# jardim.net
KiCad netlist of a schematic drawn in EAGLE
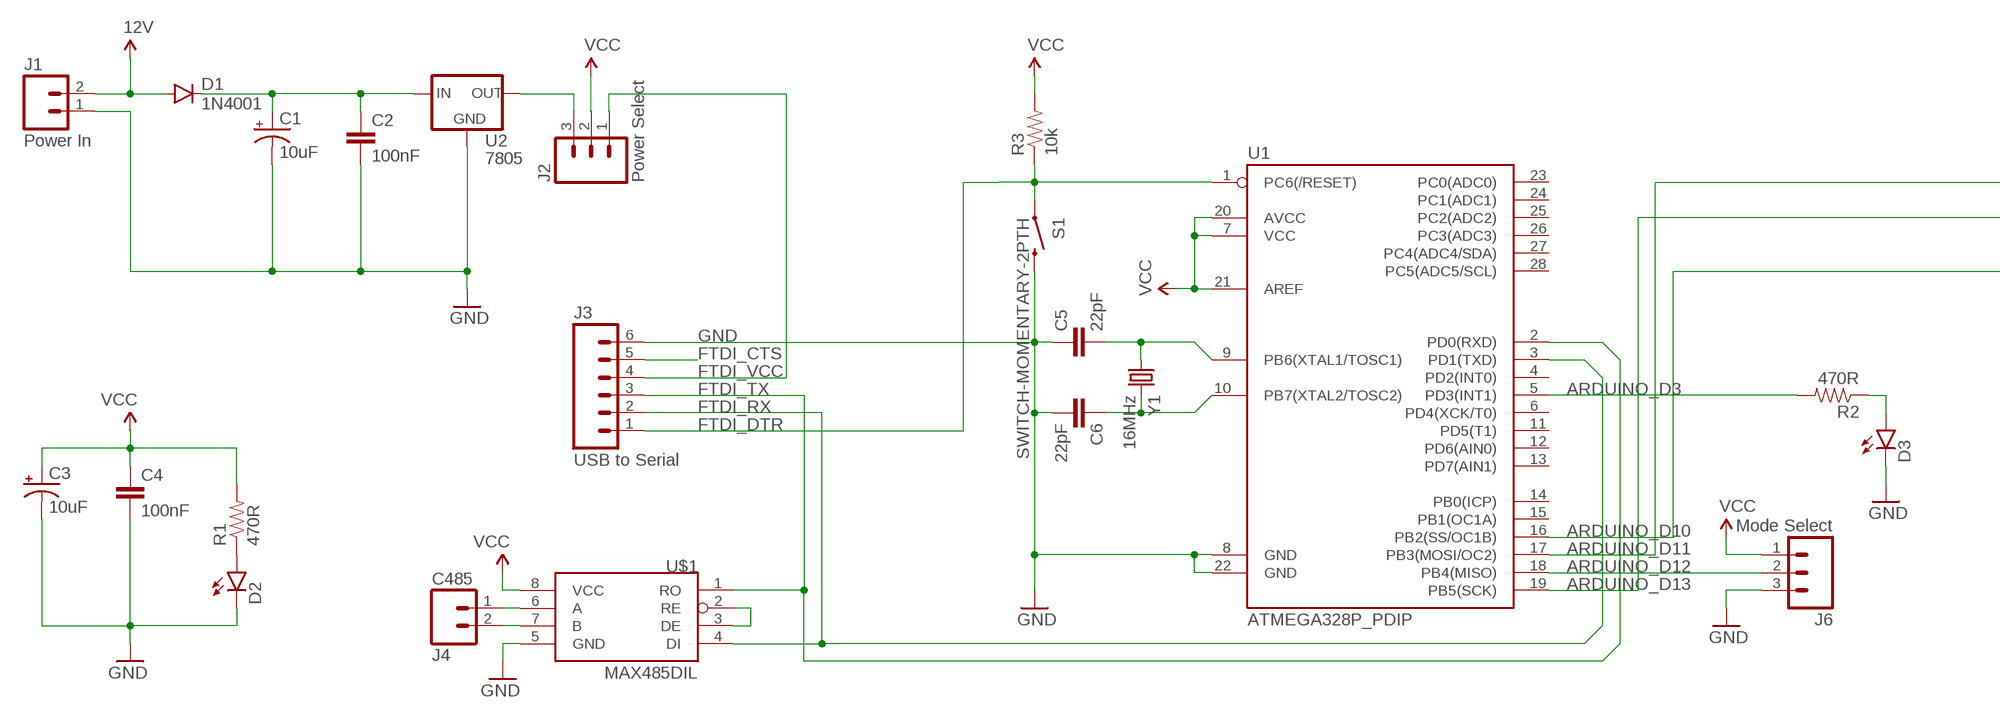
[diagram p0: schematic, sheet 1, part 1 of 2]
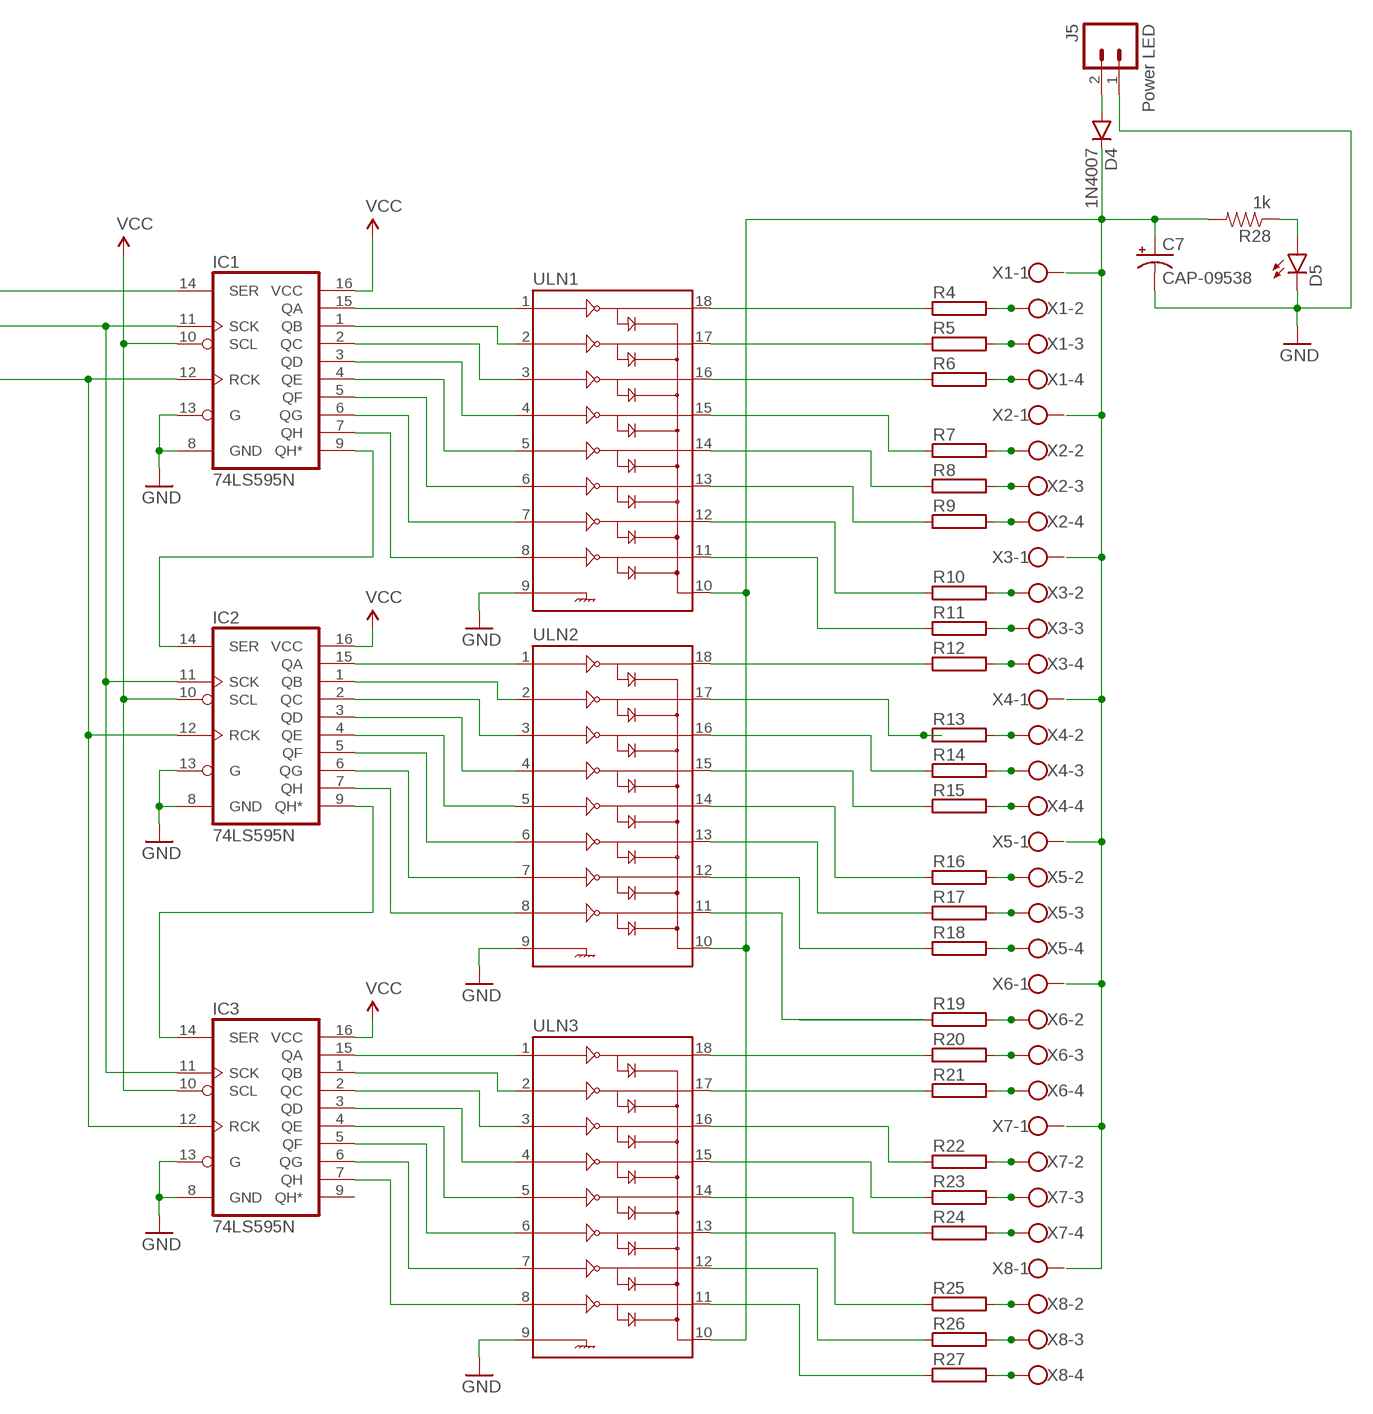
[diagram p1: schematic, sheet 1, part 2 of 2]

(export (version "E")
  (design (tool "Eeschema 10.0.6"))
  (components
    (comp (ref "C1")
      (value "10uF")
      (footprint "eagle-import:CPOL-RADIAL-10UF-25V")
      (libsource (lib "eagle-import") (part "CAP_POLPTH2"))
    )
    (comp (ref "C2")
      (value "100nF")
      (footprint "eagle-import:CAP-PTH-SMALL-KIT")
      (libsource (lib "eagle-import") (part "0.1UF-50V-20%(PTH)KIT-EZ"))
    )
    (comp (ref "C3")
      (value "10uF")
      (footprint "eagle-import:CPOL-RADIAL-10UF-25V")
      (libsource (lib "eagle-import") (part "CAP_POLPTH2"))
    )
    (comp (ref "C4")
      (value "100nF")
      (footprint "eagle-import:CAP-PTH-SMALL-KIT")
      (libsource (lib "eagle-import") (part "0.1UF-50V-20%(PTH)KIT-EZ"))
    )
    (comp (ref "C5")
      (value "22pF")
      (footprint "eagle-import:CAP-PTH-SMALL-KIT")
      (libsource (lib "eagle-import") (part "CAPKIT"))
    )
    (comp (ref "C6")
      (value "22pF")
      (footprint "eagle-import:CAP-PTH-SMALL-KIT")
      (libsource (lib "eagle-import") (part "CAPKIT"))
    )
    (comp (ref "C7")
      (value "CAP-09538")
      (footprint "eagle-import:CPOL-RADIAL-1000UF-25V")
      (libsource (lib "eagle-import") (part "1000UF-25V(PTH)"))
    )
    (comp (ref "D1")
      (value "1N4001")
      (footprint "eagle-import:DIODE-1N4001-KIT")
      (libsource (lib "eagle-import") (part "DIODEKIT2"))
    )
    (comp (ref "D2")
      (value "LED3MM")
      (footprint "eagle-import:LED3MM")
      (libsource (lib "eagle-import") (part "LED3MM"))
    )
    (comp (ref "D3")
      (value "LED3MM")
      (footprint "eagle-import:LED3MM")
      (libsource (lib "eagle-import") (part "LED3MM"))
    )
    (comp (ref "D4")
      (value "1N4007")
      (footprint "eagle-import:DIODE-1N4001")
      (libsource (lib "eagle-import") (part "DIODEPTH"))
    )
    (comp (ref "D5")
      (value "LED3MM")
      (footprint "eagle-import:LED3MM")
      (libsource (lib "eagle-import") (part "LED3MM"))
    )
    (comp (ref "IC1")
      (value "74LS595N")
      (footprint "eagle-import:DIL16")
      (libsource (lib "eagle-import") (part "74595NLS"))
    )
    (comp (ref "IC2")
      (value "74LS595N")
      (footprint "eagle-import:DIL16")
      (libsource (lib "eagle-import") (part "74595NLS"))
    )
    (comp (ref "IC3")
      (value "74LS595N")
      (footprint "eagle-import:DIL16")
      (libsource (lib "eagle-import") (part "74595NLS"))
    )
    (comp (ref "J1")
      (value "Power In")
      (footprint "eagle-import:SCREWTERMINAL-5MM-2")
      (libsource (lib "eagle-import") (part "M025MM"))
    )
    (comp (ref "J2")
      (value "Power Select")
      (footprint "eagle-import:1X03")
      (libsource (lib "eagle-import") (part "M03PTH"))
    )
    (comp (ref "J3")
      (value "USB to Serial")
      (footprint "eagle-import:1X06")
      (libsource (lib "eagle-import") (part "M06SILK_FEMALE_PTH"))
    )
    (comp (ref "J4")
      (value "C485")
      (footprint "eagle-import:SCREWTERMINAL-5MM-2")
      (libsource (lib "eagle-import") (part "M025MM"))
    )
    (comp (ref "J5")
      (value "Power LED")
      (footprint "eagle-import:SCREWTERMINAL-5MM-2")
      (libsource (lib "eagle-import") (part "M025MM"))
    )
    (comp (ref "J6")
      (value "Mode Select")
      (footprint "eagle-import:1X03")
      (libsource (lib "eagle-import") (part "M03PTH"))
    )
    (comp (ref "R1")
      (value "470R")
      (footprint "eagle-import:AXIAL-0.4")
      (libsource (lib "eagle-import") (part "RESISTORPTH-1/4W"))
    )
    (comp (ref "R2")
      (value "470R")
      (footprint "eagle-import:AXIAL-0.4")
      (libsource (lib "eagle-import") (part "RESISTORPTH-1/4W"))
    )
    (comp (ref "R3")
      (value "10k")
      (footprint "eagle-import:AXIAL-0.4")
      (libsource (lib "eagle-import") (part "RESISTORPTH-1/4W"))
    )
    (comp (ref "R4")
      (value "RCA4080")
      (footprint "eagle-import:CA4080")
      (libsource (lib "eagle-import") (part "RCA4080"))
    )
    (comp (ref "R5")
      (value "RCA4080")
      (footprint "eagle-import:CA4080")
      (libsource (lib "eagle-import") (part "RCA4080"))
    )
    (comp (ref "R6")
      (value "RCA4080")
      (footprint "eagle-import:CA4080")
      (libsource (lib "eagle-import") (part "RCA4080"))
    )
    (comp (ref "R7")
      (value "RCA4080")
      (footprint "eagle-import:CA4080")
      (libsource (lib "eagle-import") (part "RCA4080"))
    )
    (comp (ref "R8")
      (value "RCA4080")
      (footprint "eagle-import:CA4080")
      (libsource (lib "eagle-import") (part "RCA4080"))
    )
    (comp (ref "R9")
      (value "RCA4080")
      (footprint "eagle-import:CA4080")
      (libsource (lib "eagle-import") (part "RCA4080"))
    )
    (comp (ref "R10")
      (value "RCA4080")
      (footprint "eagle-import:CA4080")
      (libsource (lib "eagle-import") (part "RCA4080"))
    )
    (comp (ref "R11")
      (value "RCA4080")
      (footprint "eagle-import:CA4080")
      (libsource (lib "eagle-import") (part "RCA4080"))
    )
    (comp (ref "R12")
      (value "RCA4080")
      (footprint "eagle-import:CA4080")
      (libsource (lib "eagle-import") (part "RCA4080"))
    )
    (comp (ref "R13")
      (value "RCA4080")
      (footprint "eagle-import:CA4080")
      (libsource (lib "eagle-import") (part "RCA4080"))
    )
    (comp (ref "R14")
      (value "RCA4080")
      (footprint "eagle-import:CA4080")
      (libsource (lib "eagle-import") (part "RCA4080"))
    )
    (comp (ref "R15")
      (value "RCA4080")
      (footprint "eagle-import:CA4080")
      (libsource (lib "eagle-import") (part "RCA4080"))
    )
    (comp (ref "R16")
      (value "RCA4080")
      (footprint "eagle-import:CA4080")
      (libsource (lib "eagle-import") (part "RCA4080"))
    )
    (comp (ref "R17")
      (value "RCA4080")
      (footprint "eagle-import:CA4080")
      (libsource (lib "eagle-import") (part "RCA4080"))
    )
    (comp (ref "R18")
      (value "RCA4080")
      (footprint "eagle-import:CA4080")
      (libsource (lib "eagle-import") (part "RCA4080"))
    )
    (comp (ref "R19")
      (value "RCA4080")
      (footprint "eagle-import:CA4080")
      (libsource (lib "eagle-import") (part "RCA4080"))
    )
    (comp (ref "R20")
      (value "RCA4080")
      (footprint "eagle-import:CA4080")
      (libsource (lib "eagle-import") (part "RCA4080"))
    )
    (comp (ref "R21")
      (value "RCA4080")
      (footprint "eagle-import:CA4080")
      (libsource (lib "eagle-import") (part "RCA4080"))
    )
    (comp (ref "R22")
      (value "RCA4080")
      (footprint "eagle-import:CA4080")
      (libsource (lib "eagle-import") (part "RCA4080"))
    )
    (comp (ref "R23")
      (value "RCA4080")
      (footprint "eagle-import:CA4080")
      (libsource (lib "eagle-import") (part "RCA4080"))
    )
    (comp (ref "R24")
      (value "RCA4080")
      (footprint "eagle-import:CA4080")
      (libsource (lib "eagle-import") (part "RCA4080"))
    )
    (comp (ref "R25")
      (value "RCA4080")
      (footprint "eagle-import:CA4080")
      (libsource (lib "eagle-import") (part "RCA4080"))
    )
    (comp (ref "R26")
      (value "RCA4080")
      (footprint "eagle-import:CA4080")
      (libsource (lib "eagle-import") (part "RCA4080"))
    )
    (comp (ref "R27")
      (value "RCA4080")
      (footprint "eagle-import:CA4080")
      (libsource (lib "eagle-import") (part "RCA4080"))
    )
    (comp (ref "R28")
      (value "1k")
      (footprint "eagle-import:AXIAL-0.4")
      (libsource (lib "eagle-import") (part "RESISTORPTH-1/4W"))
    )
    (comp (ref "S1")
      (value "SWITCH-MOMENTARY-2PTH")
      (footprint "eagle-import:TACTILE-PTH")
      (libsource (lib "eagle-import") (part "SWITCH-MOMENTARY-2PTH"))
    )
    (comp (ref "U$1")
      (value "MAX485DIL")
      (footprint "eagle-import:DIL08")
      (libsource (lib "eagle-import") (part "MAX485DIL"))
    )
    (comp (ref "U1")
      (value "ATMEGA328P_PDIP")
      (footprint "eagle-import:DIL28-3")
      (libsource (lib "eagle-import") (part "ATMEGA328P_PDIP"))
    )
    (comp (ref "U2")
      (value "7805")
      (footprint "eagle-import:TO-220-ALT")
      (libsource (lib "eagle-import") (part "V_REG_78XX-TO-220"))
    )
    (comp (ref "ULN1")
      (value "ULN2803DIP")
      (footprint "eagle-import:DIL18")
      (libsource (lib "eagle-import") (part "ULN2803DIP"))
    )
    (comp (ref "ULN2")
      (value "ULN2803DIP")
      (footprint "eagle-import:DIL18")
      (libsource (lib "eagle-import") (part "ULN2803DIP"))
    )
    (comp (ref "ULN3")
      (value "ULN2803DIP")
      (footprint "eagle-import:DIL18")
      (libsource (lib "eagle-import") (part "ULN2803DIP"))
    )
    (comp (ref "X1")
      (value "W237-4")
      (footprint "eagle-import:W237-4")
      (libsource (lib "eagle-import") (part "W237-4"))
    )
    (comp (ref "X2")
      (value "W237-4")
      (footprint "eagle-import:W237-4")
      (libsource (lib "eagle-import") (part "W237-4"))
    )
    (comp (ref "X3")
      (value "W237-4")
      (footprint "eagle-import:W237-4")
      (libsource (lib "eagle-import") (part "W237-4"))
    )
    (comp (ref "X4")
      (value "W237-4")
      (footprint "eagle-import:W237-4")
      (libsource (lib "eagle-import") (part "W237-4"))
    )
    (comp (ref "X5")
      (value "W237-4")
      (footprint "eagle-import:W237-4")
      (libsource (lib "eagle-import") (part "W237-4"))
    )
    (comp (ref "X6")
      (value "W237-4")
      (footprint "eagle-import:W237-4")
      (libsource (lib "eagle-import") (part "W237-4"))
    )
    (comp (ref "X7")
      (value "W237-4")
      (footprint "eagle-import:W237-4")
      (libsource (lib "eagle-import") (part "W237-4"))
    )
    (comp (ref "X8")
      (value "W237-4")
      (footprint "eagle-import:W237-4")
      (libsource (lib "eagle-import") (part "W237-4"))
    )
    (comp (ref "Y1")
      (value "16MHz")
      (footprint "eagle-import:HC49US")
      (libsource (lib "eagle-import") (part "CRYSTALHC49US"))
    )
  )
  (nets
    (net (code "1") (name "/ARDUINO_D3") (class "Default")
      (node (ref "R2") (pin "P$2") (pinfunction "2_P$2") (pintype "passive"))
      (node (ref "U1") (pin "5") (pinfunction "PD3(INT1)_5") (pintype "bidirectional"))
    )
    (net (code "2") (name "/ARDUINO_D10") (class "Default")
      (node (ref "IC1") (pin "12") (pinfunction "RCK_12") (pintype "input"))
      (node (ref "IC2") (pin "12") (pinfunction "RCK_12") (pintype "input"))
      (node (ref "IC3") (pin "12") (pinfunction "RCK_12") (pintype "input"))
      (node (ref "U1") (pin "16") (pinfunction "PB2(SS/OC1B)_16") (pintype "bidirectional"))
    )
    (net (code "3") (name "/ARDUINO_D11") (class "Default")
      (node (ref "IC1") (pin "14") (pinfunction "SER_14") (pintype "input"))
      (node (ref "U1") (pin "17") (pinfunction "PB3(MOSI/OC2)_17") (pintype "bidirectional"))
    )
    (net (code "4") (name "/ARDUINO_D12") (class "Default")
      (node (ref "J6") (pin "2") (pinfunction "2_2") (pintype "passive"))
      (node (ref "U1") (pin "18") (pinfunction "PB4(MISO)_18") (pintype "bidirectional"))
    )
    (net (code "5") (name "/ARDUINO_D13") (class "Default")
      (node (ref "IC1") (pin "11") (pinfunction "SCK_11") (pintype "input"))
      (node (ref "IC2") (pin "11") (pinfunction "SCK_11") (pintype "input"))
      (node (ref "IC3") (pin "11") (pinfunction "SCK_11") (pintype "input"))
      (node (ref "U1") (pin "19") (pinfunction "PB5(SCK)_19") (pintype "bidirectional"))
    )
    (net (code "6") (name "/FTDI_CTS") (class "Default")
      (node (ref "J3") (pin "5") (pinfunction "5_5") (pintype "passive"))
    )
    (net (code "7") (name "/FTDI_DTR") (class "Default")
      (node (ref "J3") (pin "1") (pinfunction "1_1") (pintype "passive"))
      (node (ref "R3") (pin "P$1") (pinfunction "1_P$1") (pintype "passive"))
      (node (ref "S1") (pin "1") (pinfunction "1_1") (pintype "passive"))
      (node (ref "U1") (pin "1") (pinfunction "PC6(/RESET)_1") (pintype "bidirectional"))
    )
    (net (code "8") (name "/FTDI_RX") (class "Default")
      (node (ref "J3") (pin "2") (pinfunction "2_2") (pintype "passive"))
      (node (ref "U$1") (pin "4") (pinfunction "DI_4") (pintype "bidirectional"))
      (node (ref "U1") (pin "3") (pinfunction "PD1(TXD)_3") (pintype "bidirectional"))
    )
    (net (code "9") (name "/FTDI_TX") (class "Default")
      (node (ref "J3") (pin "3") (pinfunction "3_3") (pintype "passive"))
      (node (ref "U$1") (pin "1") (pinfunction "RO_1") (pintype "bidirectional"))
      (node (ref "U1") (pin "2") (pinfunction "PD0(RXD)_2") (pintype "bidirectional"))
    )
    (net (code "10") (name "/FTDI_VCC") (class "Default")
      (node (ref "J2") (pin "1") (pinfunction "1_1") (pintype "passive"))
      (node (ref "J3") (pin "4") (pinfunction "4_4") (pintype "passive"))
    )
    (net (code "11") (name "12V") (class "Default")
      (node (ref "D1") (pin "A") (pinfunction "A_A") (pintype "passive"))
      (node (ref "J1") (pin "2") (pinfunction "2_2") (pintype "passive"))
    )
    (net (code "12") (name "GND") (class "Default")
      (node (ref "C1") (pin "2") (pinfunction "-_2") (pintype "passive"))
      (node (ref "C2") (pin "2") (pinfunction "2_2") (pintype "passive"))
      (node (ref "C3") (pin "2") (pinfunction "-_2") (pintype "passive"))
      (node (ref "C4") (pin "2") (pinfunction "2_2") (pintype "passive"))
      (node (ref "C5") (pin "1") (pinfunction "1_1") (pintype "passive"))
      (node (ref "C6") (pin "2") (pinfunction "2_2") (pintype "passive"))
      (node (ref "C7") (pin "-") (pinfunction "-_-") (pintype "passive"))
      (node (ref "D2") (pin "K") (pinfunction "C_K") (pintype "passive"))
      (node (ref "D3") (pin "K") (pinfunction "C_K") (pintype "passive"))
      (node (ref "D5") (pin "K") (pinfunction "C_K") (pintype "passive"))
      (node (ref "IC1") (pin "13") (pinfunction "G_13") (pintype "input"))
      (node (ref "IC1") (pin "8") (pinfunction "GND_8") (pintype "power_in"))
      (node (ref "IC2") (pin "13") (pinfunction "G_13") (pintype "input"))
      (node (ref "IC2") (pin "8") (pinfunction "GND_8") (pintype "power_in"))
      (node (ref "IC3") (pin "13") (pinfunction "G_13") (pintype "input"))
      (node (ref "IC3") (pin "8") (pinfunction "GND_8") (pintype "power_in"))
      (node (ref "J1") (pin "1") (pinfunction "1_1") (pintype "passive"))
      (node (ref "J3") (pin "6") (pinfunction "6_6") (pintype "passive"))
      (node (ref "J5") (pin "1") (pinfunction "1_1") (pintype "passive"))
      (node (ref "J6") (pin "3") (pinfunction "3_3") (pintype "passive"))
      (node (ref "S1") (pin "3") (pinfunction "2_3") (pintype "passive"))
      (node (ref "U$1") (pin "5") (pinfunction "GND_5") (pintype "bidirectional"))
      (node (ref "U1") (pin "22") (pinfunction "GND_22") (pintype "bidirectional"))
      (node (ref "U1") (pin "8") (pinfunction "GND_8") (pintype "bidirectional"))
      (node (ref "U2") (pin "GND") (pinfunction "GND_GND") (pintype "input"))
      (node (ref "ULN1") (pin "9") (pinfunction "9_9") (pintype "bidirectional"))
      (node (ref "ULN2") (pin "9") (pinfunction "9_9") (pintype "bidirectional"))
      (node (ref "ULN3") (pin "9") (pinfunction "9_9") (pintype "bidirectional"))
    )
    (net (code "13") (name "Net-(C1-+)") (class "Default")
      (node (ref "C1") (pin "1") (pinfunction "+_1") (pintype "passive"))
      (node (ref "C2") (pin "1") (pinfunction "1_1") (pintype "passive"))
      (node (ref "D1") (pin "C") (pinfunction "C_C") (pintype "passive"))
      (node (ref "U2") (pin "IN") (pinfunction "IN_IN") (pintype "input"))
    )
    (net (code "14") (name "Net-(D4-PadA)") (class "Default")
      (node (ref "D4") (pin "A") (pinfunction "A_A") (pintype "passive"))
      (node (ref "J5") (pin "2") (pinfunction "2_2") (pintype "passive"))
    )
    (net (code "15") (name "Net-(IC1-QA)") (class "Default")
      (node (ref "IC1") (pin "15") (pinfunction "QA_15") (pintype "tri_state"))
      (node (ref "ULN1") (pin "1") (pinfunction "1_1") (pintype "bidirectional"))
    )
    (net (code "16") (name "Net-(IC1-QB)") (class "Default")
      (node (ref "IC1") (pin "1") (pinfunction "QB_1") (pintype "tri_state"))
      (node (ref "ULN1") (pin "2") (pinfunction "2_2") (pintype "bidirectional"))
    )
    (net (code "17") (name "Net-(IC1-QC)") (class "Default")
      (node (ref "IC1") (pin "2") (pinfunction "QC_2") (pintype "tri_state"))
      (node (ref "ULN1") (pin "3") (pinfunction "3_3") (pintype "bidirectional"))
    )
    (net (code "18") (name "Net-(IC1-QD)") (class "Default")
      (node (ref "IC1") (pin "3") (pinfunction "QD_3") (pintype "tri_state"))
      (node (ref "ULN1") (pin "4") (pinfunction "4_4") (pintype "bidirectional"))
    )
    (net (code "19") (name "Net-(IC1-QE)") (class "Default")
      (node (ref "IC1") (pin "4") (pinfunction "QE_4") (pintype "tri_state"))
      (node (ref "ULN1") (pin "5") (pinfunction "5_5") (pintype "bidirectional"))
    )
    (net (code "20") (name "Net-(IC1-QF)") (class "Default")
      (node (ref "IC1") (pin "5") (pinfunction "QF_5") (pintype "tri_state"))
      (node (ref "ULN1") (pin "6") (pinfunction "6_6") (pintype "bidirectional"))
    )
    (net (code "21") (name "Net-(IC1-QG)") (class "Default")
      (node (ref "IC1") (pin "6") (pinfunction "QG_6") (pintype "tri_state"))
      (node (ref "ULN1") (pin "7") (pinfunction "7_7") (pintype "bidirectional"))
    )
    (net (code "22") (name "Net-(IC1-QH)") (class "Default")
      (node (ref "IC1") (pin "7") (pinfunction "QH_7") (pintype "tri_state"))
      (node (ref "ULN1") (pin "8") (pinfunction "8_8") (pintype "bidirectional"))
    )
    (net (code "23") (name "Net-(IC1-QH*)") (class "Default")
      (node (ref "IC1") (pin "9") (pinfunction "QH*_9") (pintype "tri_state"))
      (node (ref "IC2") (pin "14") (pinfunction "SER_14") (pintype "input"))
    )
    (net (code "24") (name "Net-(IC2-QA)") (class "Default")
      (node (ref "IC2") (pin "15") (pinfunction "QA_15") (pintype "tri_state"))
      (node (ref "ULN2") (pin "1") (pinfunction "1_1") (pintype "bidirectional"))
    )
    (net (code "25") (name "Net-(IC2-QB)") (class "Default")
      (node (ref "IC2") (pin "1") (pinfunction "QB_1") (pintype "tri_state"))
      (node (ref "ULN2") (pin "2") (pinfunction "2_2") (pintype "bidirectional"))
    )
    (net (code "26") (name "Net-(IC2-QC)") (class "Default")
      (node (ref "IC2") (pin "2") (pinfunction "QC_2") (pintype "tri_state"))
      (node (ref "ULN2") (pin "3") (pinfunction "3_3") (pintype "bidirectional"))
    )
    (net (code "27") (name "Net-(IC2-QD)") (class "Default")
      (node (ref "IC2") (pin "3") (pinfunction "QD_3") (pintype "tri_state"))
      (node (ref "ULN2") (pin "4") (pinfunction "4_4") (pintype "bidirectional"))
    )
    (net (code "28") (name "Net-(IC2-QE)") (class "Default")
      (node (ref "IC2") (pin "4") (pinfunction "QE_4") (pintype "tri_state"))
      (node (ref "ULN2") (pin "5") (pinfunction "5_5") (pintype "bidirectional"))
    )
    (net (code "29") (name "Net-(IC2-QF)") (class "Default")
      (node (ref "IC2") (pin "5") (pinfunction "QF_5") (pintype "tri_state"))
      (node (ref "ULN2") (pin "6") (pinfunction "6_6") (pintype "bidirectional"))
    )
    (net (code "30") (name "Net-(IC2-QG)") (class "Default")
      (node (ref "IC2") (pin "6") (pinfunction "QG_6") (pintype "tri_state"))
      (node (ref "ULN2") (pin "7") (pinfunction "7_7") (pintype "bidirectional"))
    )
    (net (code "31") (name "Net-(IC2-QH)") (class "Default")
      (node (ref "IC2") (pin "7") (pinfunction "QH_7") (pintype "tri_state"))
      (node (ref "ULN2") (pin "8") (pinfunction "8_8") (pintype "bidirectional"))
    )
    (net (code "32") (name "Net-(IC2-QH*)") (class "Default")
      (node (ref "IC2") (pin "9") (pinfunction "QH*_9") (pintype "tri_state"))
      (node (ref "IC3") (pin "14") (pinfunction "SER_14") (pintype "input"))
    )
    (net (code "33") (name "Net-(IC3-QA)") (class "Default")
      (node (ref "IC3") (pin "15") (pinfunction "QA_15") (pintype "tri_state"))
      (node (ref "ULN3") (pin "1") (pinfunction "1_1") (pintype "bidirectional"))
    )
    (net (code "34") (name "Net-(IC3-QB)") (class "Default")
      (node (ref "IC3") (pin "1") (pinfunction "QB_1") (pintype "tri_state"))
      (node (ref "ULN3") (pin "2") (pinfunction "2_2") (pintype "bidirectional"))
    )
    (net (code "35") (name "Net-(IC3-QC)") (class "Default")
      (node (ref "IC3") (pin "2") (pinfunction "QC_2") (pintype "tri_state"))
      (node (ref "ULN3") (pin "3") (pinfunction "3_3") (pintype "bidirectional"))
    )
    (net (code "36") (name "Net-(IC3-QD)") (class "Default")
      (node (ref "IC3") (pin "3") (pinfunction "QD_3") (pintype "tri_state"))
      (node (ref "ULN3") (pin "4") (pinfunction "4_4") (pintype "bidirectional"))
    )
    (net (code "37") (name "Net-(IC3-QE)") (class "Default")
      (node (ref "IC3") (pin "4") (pinfunction "QE_4") (pintype "tri_state"))
      (node (ref "ULN3") (pin "5") (pinfunction "5_5") (pintype "bidirectional"))
    )
    (net (code "38") (name "Net-(IC3-QF)") (class "Default")
      (node (ref "IC3") (pin "5") (pinfunction "QF_5") (pintype "tri_state"))
      (node (ref "ULN3") (pin "6") (pinfunction "6_6") (pintype "bidirectional"))
    )
    (net (code "39") (name "Net-(IC3-QG)") (class "Default")
      (node (ref "IC3") (pin "6") (pinfunction "QG_6") (pintype "tri_state"))
      (node (ref "ULN3") (pin "7") (pinfunction "7_7") (pintype "bidirectional"))
    )
    (net (code "40") (name "Net-(IC3-QH)") (class "Default")
      (node (ref "IC3") (pin "7") (pinfunction "QH_7") (pintype "tri_state"))
      (node (ref "ULN3") (pin "8") (pinfunction "8_8") (pintype "bidirectional"))
    )
    (net (code "41") (name "Net-(J2-Pad3)") (class "Default")
      (node (ref "J2") (pin "3") (pinfunction "3_3") (pintype "passive"))
      (node (ref "U2") (pin "OUT") (pinfunction "OUT_OUT") (pintype "passive"))
    )
    (net (code "42") (name "Net-(R1-1)") (class "Default")
      (node (ref "D2") (pin "A") (pinfunction "A_A") (pintype "passive"))
      (node (ref "R1") (pin "P$1") (pinfunction "1_P$1") (pintype "passive"))
    )
    (net (code "43") (name "Net-(R2-1)") (class "Default")
      (node (ref "D3") (pin "A") (pinfunction "A_A") (pintype "passive"))
      (node (ref "R2") (pin "P$1") (pinfunction "1_P$1") (pintype "passive"))
    )
    (net (code "44") (name "Net-(R4-Pad1)") (class "Default")
      (node (ref "R4") (pin "1") (pinfunction "1_1") (pintype "passive"))
      (node (ref "ULN1") (pin "18") (pinfunction "18_18") (pintype "bidirectional"))
    )
    (net (code "45") (name "Net-(R5-Pad1)") (class "Default")
      (node (ref "R5") (pin "1") (pinfunction "1_1") (pintype "passive"))
      (node (ref "ULN1") (pin "17") (pinfunction "17_17") (pintype "bidirectional"))
    )
    (net (code "46") (name "Net-(R6-Pad1)") (class "Default")
      (node (ref "R6") (pin "1") (pinfunction "1_1") (pintype "passive"))
      (node (ref "ULN1") (pin "16") (pinfunction "16_16") (pintype "bidirectional"))
    )
    (net (code "47") (name "Net-(R7-Pad1)") (class "Default")
      (node (ref "R7") (pin "1") (pinfunction "1_1") (pintype "passive"))
      (node (ref "ULN1") (pin "15") (pinfunction "15_15") (pintype "bidirectional"))
    )
    (net (code "48") (name "Net-(R8-Pad1)") (class "Default")
      (node (ref "R8") (pin "1") (pinfunction "1_1") (pintype "passive"))
      (node (ref "ULN1") (pin "14") (pinfunction "14_14") (pintype "bidirectional"))
    )
    (net (code "49") (name "Net-(R9-Pad1)") (class "Default")
      (node (ref "R9") (pin "1") (pinfunction "1_1") (pintype "passive"))
      (node (ref "ULN1") (pin "13") (pinfunction "13_13") (pintype "bidirectional"))
    )
    (net (code "50") (name "Net-(R10-Pad1)") (class "Default")
      (node (ref "R10") (pin "1") (pinfunction "1_1") (pintype "passive"))
      (node (ref "ULN1") (pin "12") (pinfunction "12_12") (pintype "bidirectional"))
    )
    (net (code "51") (name "Net-(R11-Pad1)") (class "Default")
      (node (ref "R11") (pin "1") (pinfunction "1_1") (pintype "passive"))
      (node (ref "ULN1") (pin "11") (pinfunction "11_11") (pintype "bidirectional"))
    )
    (net (code "52") (name "Net-(R12-Pad1)") (class "Default")
      (node (ref "R12") (pin "1") (pinfunction "1_1") (pintype "passive"))
      (node (ref "ULN2") (pin "18") (pinfunction "18_18") (pintype "bidirectional"))
    )
    (net (code "53") (name "Net-(R13-Pad1)") (class "Default")
      (node (ref "R13") (pin "1") (pinfunction "1_1") (pintype "passive"))
      (node (ref "ULN2") (pin "17") (pinfunction "17_17") (pintype "bidirectional"))
    )
    (net (code "54") (name "Net-(R14-Pad1)") (class "Default")
      (node (ref "R14") (pin "1") (pinfunction "1_1") (pintype "passive"))
      (node (ref "ULN2") (pin "16") (pinfunction "16_16") (pintype "bidirectional"))
    )
    (net (code "55") (name "Net-(R15-Pad1)") (class "Default")
      (node (ref "R15") (pin "1") (pinfunction "1_1") (pintype "passive"))
      (node (ref "ULN2") (pin "15") (pinfunction "15_15") (pintype "bidirectional"))
    )
    (net (code "56") (name "Net-(R16-Pad1)") (class "Default")
      (node (ref "R16") (pin "1") (pinfunction "1_1") (pintype "passive"))
      (node (ref "ULN2") (pin "14") (pinfunction "14_14") (pintype "bidirectional"))
    )
    (net (code "57") (name "Net-(R17-Pad1)") (class "Default")
      (node (ref "R17") (pin "1") (pinfunction "1_1") (pintype "passive"))
      (node (ref "ULN2") (pin "13") (pinfunction "13_13") (pintype "bidirectional"))
    )
    (net (code "58") (name "Net-(R18-Pad1)") (class "Default")
      (node (ref "R18") (pin "1") (pinfunction "1_1") (pintype "passive"))
      (node (ref "ULN2") (pin "12") (pinfunction "12_12") (pintype "bidirectional"))
    )
    (net (code "59") (name "Net-(R19-Pad1)") (class "Default")
      (node (ref "R19") (pin "1") (pinfunction "1_1") (pintype "passive"))
      (node (ref "ULN2") (pin "11") (pinfunction "11_11") (pintype "bidirectional"))
    )
    (net (code "60") (name "Net-(R20-Pad1)") (class "Default")
      (node (ref "R20") (pin "1") (pinfunction "1_1") (pintype "passive"))
      (node (ref "ULN3") (pin "18") (pinfunction "18_18") (pintype "bidirectional"))
    )
    (net (code "61") (name "Net-(R21-Pad1)") (class "Default")
      (node (ref "R21") (pin "1") (pinfunction "1_1") (pintype "passive"))
      (node (ref "ULN3") (pin "17") (pinfunction "17_17") (pintype "bidirectional"))
    )
    (net (code "62") (name "Net-(R22-Pad1)") (class "Default")
      (node (ref "R22") (pin "1") (pinfunction "1_1") (pintype "passive"))
      (node (ref "ULN3") (pin "16") (pinfunction "16_16") (pintype "bidirectional"))
    )
    (net (code "63") (name "Net-(R23-Pad1)") (class "Default")
      (node (ref "R23") (pin "1") (pinfunction "1_1") (pintype "passive"))
      (node (ref "ULN3") (pin "15") (pinfunction "15_15") (pintype "bidirectional"))
    )
    (net (code "64") (name "Net-(R24-Pad1)") (class "Default")
      (node (ref "R24") (pin "1") (pinfunction "1_1") (pintype "passive"))
      (node (ref "ULN3") (pin "14") (pinfunction "14_14") (pintype "bidirectional"))
    )
    (net (code "65") (name "Net-(R25-Pad1)") (class "Default")
      (node (ref "R25") (pin "1") (pinfunction "1_1") (pintype "passive"))
      (node (ref "ULN3") (pin "13") (pinfunction "13_13") (pintype "bidirectional"))
    )
    (net (code "66") (name "Net-(R26-Pad1)") (class "Default")
      (node (ref "R26") (pin "1") (pinfunction "1_1") (pintype "passive"))
      (node (ref "ULN3") (pin "12") (pinfunction "12_12") (pintype "bidirectional"))
    )
    (net (code "67") (name "Net-(R27-Pad1)") (class "Default")
      (node (ref "R27") (pin "1") (pinfunction "1_1") (pintype "passive"))
      (node (ref "ULN3") (pin "11") (pinfunction "11_11") (pintype "bidirectional"))
    )
    (net (code "68") (name "Net-(R28-1)") (class "Default")
      (node (ref "D5") (pin "A") (pinfunction "A_A") (pintype "passive"))
      (node (ref "R28") (pin "P$1") (pinfunction "1_P$1") (pintype "passive"))
    )
    (net (code "69") (name "Net-(R28-2)") (class "Default")
      (node (ref "C7") (pin "+") (pinfunction "+_+") (pintype "passive"))
      (node (ref "D4") (pin "C") (pinfunction "C_C") (pintype "passive"))
      (node (ref "R28") (pin "P$2") (pinfunction "2_P$2") (pintype "passive"))
      (node (ref "ULN1") (pin "10") (pinfunction "10_10") (pintype "bidirectional"))
      (node (ref "ULN2") (pin "10") (pinfunction "10_10") (pintype "bidirectional"))
      (node (ref "ULN3") (pin "10") (pinfunction "10_10") (pintype "bidirectional"))
    )
    (net (code "70") (name "Net-(U$1-A)") (class "Default")
      (node (ref "J4") (pin "1") (pinfunction "1_1") (pintype "passive"))
      (node (ref "U$1") (pin "6") (pinfunction "A_6") (pintype "bidirectional"))
    )
    (net (code "71") (name "Net-(U$1-B)") (class "Default")
      (node (ref "J4") (pin "2") (pinfunction "2_2") (pintype "passive"))
      (node (ref "U$1") (pin "7") (pinfunction "B_7") (pintype "bidirectional"))
    )
    (net (code "72") (name "Net-(U$1-DE)") (class "Default")
      (node (ref "U$1") (pin "2") (pinfunction "RE_2") (pintype "bidirectional"))
      (node (ref "U$1") (pin "3") (pinfunction "DE_3") (pintype "bidirectional"))
    )
    (net (code "73") (name "Net-(U1-PB6(XTAL1{slash}TOSC1))") (class "Default")
      (node (ref "C5") (pin "2") (pinfunction "2_2") (pintype "passive"))
      (node (ref "U1") (pin "9") (pinfunction "PB6(XTAL1/TOSC1)_9") (pintype "bidirectional"))
      (node (ref "Y1") (pin "1") (pinfunction "1_1") (pintype "passive"))
    )
    (net (code "74") (name "Net-(U1-PB7(XTAL2{slash}TOSC2))") (class "Default")
      (node (ref "C6") (pin "1") (pinfunction "1_1") (pintype "passive"))
      (node (ref "U1") (pin "10") (pinfunction "PB7(XTAL2/TOSC2)_10") (pintype "bidirectional"))
      (node (ref "Y1") (pin "2") (pinfunction "2_2") (pintype "passive"))
    )
    (net (code "75") (name "Net-(X1B-KL)") (class "Default")
      (node (ref "R4") (pin "2") (pinfunction "2_2") (pintype "passive"))
      (node (ref "X1") (pin "2") (pinfunction "KL_2") (pintype "passive"))
    )
    (net (code "76") (name "Net-(X1C-KL)") (class "Default")
      (node (ref "R5") (pin "2") (pinfunction "2_2") (pintype "passive"))
      (node (ref "X1") (pin "3") (pinfunction "KL_3") (pintype "passive"))
    )
    (net (code "77") (name "Net-(X1D-KL)") (class "Default")
      (node (ref "R6") (pin "2") (pinfunction "2_2") (pintype "passive"))
      (node (ref "X1") (pin "4") (pinfunction "KL_4") (pintype "passive"))
    )
    (net (code "78") (name "Net-(X2B-KL)") (class "Default")
      (node (ref "R7") (pin "2") (pinfunction "2_2") (pintype "passive"))
      (node (ref "X2") (pin "2") (pinfunction "KL_2") (pintype "passive"))
    )
    (net (code "79") (name "Net-(X2C-KL)") (class "Default")
      (node (ref "R8") (pin "2") (pinfunction "2_2") (pintype "passive"))
      (node (ref "X2") (pin "3") (pinfunction "KL_3") (pintype "passive"))
    )
    (net (code "80") (name "Net-(X2D-KL)") (class "Default")
      (node (ref "R9") (pin "2") (pinfunction "2_2") (pintype "passive"))
      (node (ref "X2") (pin "4") (pinfunction "KL_4") (pintype "passive"))
    )
    (net (code "81") (name "Net-(X3B-KL)") (class "Default")
      (node (ref "R10") (pin "2") (pinfunction "2_2") (pintype "passive"))
      (node (ref "X3") (pin "2") (pinfunction "KL_2") (pintype "passive"))
    )
    (net (code "82") (name "Net-(X3C-KL)") (class "Default")
      (node (ref "R11") (pin "2") (pinfunction "2_2") (pintype "passive"))
      (node (ref "X3") (pin "3") (pinfunction "KL_3") (pintype "passive"))
    )
    (net (code "83") (name "Net-(X3D-KL)") (class "Default")
      (node (ref "R12") (pin "2") (pinfunction "2_2") (pintype "passive"))
      (node (ref "X3") (pin "4") (pinfunction "KL_4") (pintype "passive"))
    )
    (net (code "84") (name "Net-(X4B-KL)") (class "Default")
      (node (ref "R13") (pin "2") (pinfunction "2_2") (pintype "passive"))
      (node (ref "X4") (pin "2") (pinfunction "KL_2") (pintype "passive"))
    )
    (net (code "85") (name "Net-(X4C-KL)") (class "Default")
      (node (ref "R14") (pin "2") (pinfunction "2_2") (pintype "passive"))
      (node (ref "X4") (pin "3") (pinfunction "KL_3") (pintype "passive"))
    )
    (net (code "86") (name "Net-(X4D-KL)") (class "Default")
      (node (ref "R15") (pin "2") (pinfunction "2_2") (pintype "passive"))
      (node (ref "X4") (pin "4") (pinfunction "KL_4") (pintype "passive"))
    )
    (net (code "87") (name "Net-(X5B-KL)") (class "Default")
      (node (ref "R16") (pin "2") (pinfunction "2_2") (pintype "passive"))
      (node (ref "X5") (pin "2") (pinfunction "KL_2") (pintype "passive"))
    )
    (net (code "88") (name "Net-(X5C-KL)") (class "Default")
      (node (ref "R17") (pin "2") (pinfunction "2_2") (pintype "passive"))
      (node (ref "X5") (pin "3") (pinfunction "KL_3") (pintype "passive"))
    )
    (net (code "89") (name "Net-(X5D-KL)") (class "Default")
      (node (ref "R18") (pin "2") (pinfunction "2_2") (pintype "passive"))
      (node (ref "X5") (pin "4") (pinfunction "KL_4") (pintype "passive"))
    )
    (net (code "90") (name "Net-(X6B-KL)") (class "Default")
      (node (ref "R19") (pin "2") (pinfunction "2_2") (pintype "passive"))
      (node (ref "X6") (pin "2") (pinfunction "KL_2") (pintype "passive"))
    )
    (net (code "91") (name "Net-(X6C-KL)") (class "Default")
      (node (ref "R20") (pin "2") (pinfunction "2_2") (pintype "passive"))
      (node (ref "X6") (pin "3") (pinfunction "KL_3") (pintype "passive"))
    )
    (net (code "92") (name "Net-(X6D-KL)") (class "Default")
      (node (ref "R21") (pin "2") (pinfunction "2_2") (pintype "passive"))
      (node (ref "X6") (pin "4") (pinfunction "KL_4") (pintype "passive"))
    )
    (net (code "93") (name "Net-(X7B-KL)") (class "Default")
      (node (ref "R22") (pin "2") (pinfunction "2_2") (pintype "passive"))
      (node (ref "X7") (pin "2") (pinfunction "KL_2") (pintype "passive"))
    )
    (net (code "94") (name "Net-(X7C-KL)") (class "Default")
      (node (ref "R23") (pin "2") (pinfunction "2_2") (pintype "passive"))
      (node (ref "X7") (pin "3") (pinfunction "KL_3") (pintype "passive"))
    )
    (net (code "95") (name "Net-(X7D-KL)") (class "Default")
      (node (ref "R24") (pin "2") (pinfunction "2_2") (pintype "passive"))
      (node (ref "X7") (pin "4") (pinfunction "KL_4") (pintype "passive"))
    )
    (net (code "96") (name "Net-(X8B-KL)") (class "Default")
      (node (ref "R25") (pin "2") (pinfunction "2_2") (pintype "passive"))
      (node (ref "X8") (pin "2") (pinfunction "KL_2") (pintype "passive"))
    )
    (net (code "97") (name "Net-(X8C-KL)") (class "Default")
      (node (ref "R26") (pin "2") (pinfunction "2_2") (pintype "passive"))
      (node (ref "X8") (pin "3") (pinfunction "KL_3") (pintype "passive"))
    )
    (net (code "98") (name "Net-(X8D-KL)") (class "Default")
      (node (ref "R27") (pin "2") (pinfunction "2_2") (pintype "passive"))
      (node (ref "X8") (pin "4") (pinfunction "KL_4") (pintype "passive"))
    )
    (net (code "99") (name "VCC") (class "Default")
      (node (ref "C3") (pin "1") (pinfunction "+_1") (pintype "passive"))
      (node (ref "C4") (pin "1") (pinfunction "1_1") (pintype "passive"))
      (node (ref "IC1") (pin "10") (pinfunction "SCL_10") (pintype "input"))
      (node (ref "IC1") (pin "16") (pinfunction "VCC_16") (pintype "power_in"))
      (node (ref "IC2") (pin "10") (pinfunction "SCL_10") (pintype "input"))
      (node (ref "IC2") (pin "16") (pinfunction "VCC_16") (pintype "power_in"))
      (node (ref "IC3") (pin "10") (pinfunction "SCL_10") (pintype "input"))
      (node (ref "IC3") (pin "16") (pinfunction "VCC_16") (pintype "power_in"))
      (node (ref "J2") (pin "2") (pinfunction "2_2") (pintype "passive"))
      (node (ref "J6") (pin "1") (pinfunction "1_1") (pintype "passive"))
      (node (ref "R1") (pin "P$2") (pinfunction "2_P$2") (pintype "passive"))
      (node (ref "R3") (pin "P$2") (pinfunction "2_P$2") (pintype "passive"))
      (node (ref "U$1") (pin "8") (pinfunction "VCC_8") (pintype "bidirectional"))
      (node (ref "U1") (pin "20") (pinfunction "AVCC_20") (pintype "bidirectional"))
      (node (ref "U1") (pin "21") (pinfunction "AREF_21") (pintype "bidirectional"))
      (node (ref "U1") (pin "7") (pinfunction "VCC_7") (pintype "bidirectional"))
    )
    (net (code "100") (name "unconnected-(IC3-QH*-Pad9)") (class "Default")
      (node (ref "IC3") (pin "9") (pinfunction "QH*_9") (pintype "tri_state"))
    )
    (net (code "101") (name "unconnected-(U1-PB0(ICP)-Pad14)") (class "Default")
      (node (ref "U1") (pin "14") (pinfunction "PB0(ICP)_14") (pintype "bidirectional"))
    )
    (net (code "102") (name "unconnected-(U1-PB1(OC1A)-Pad15)") (class "Default")
      (node (ref "U1") (pin "15") (pinfunction "PB1(OC1A)_15") (pintype "bidirectional"))
    )
    (net (code "103") (name "unconnected-(U1-PC0(ADC0)-Pad23)") (class "Default")
      (node (ref "U1") (pin "23") (pinfunction "PC0(ADC0)_23") (pintype "bidirectional"))
    )
    (net (code "104") (name "unconnected-(U1-PC1(ADC1)-Pad24)") (class "Default")
      (node (ref "U1") (pin "24") (pinfunction "PC1(ADC1)_24") (pintype "bidirectional"))
    )
    (net (code "105") (name "unconnected-(U1-PC2(ADC2)-Pad25)") (class "Default")
      (node (ref "U1") (pin "25") (pinfunction "PC2(ADC2)_25") (pintype "bidirectional"))
    )
    (net (code "106") (name "unconnected-(U1-PC3(ADC3)-Pad26)") (class "Default")
      (node (ref "U1") (pin "26") (pinfunction "PC3(ADC3)_26") (pintype "bidirectional"))
    )
    (net (code "107") (name "unconnected-(U1-PC4(ADC4{slash}SDA)-Pad27)") (class "Default")
      (node (ref "U1") (pin "27") (pinfunction "PC4(ADC4/SDA)_27") (pintype "bidirectional"))
    )
    (net (code "108") (name "unconnected-(U1-PC5(ADC5{slash}SCL)-Pad28)") (class "Default")
      (node (ref "U1") (pin "28") (pinfunction "PC5(ADC5/SCL)_28") (pintype "bidirectional"))
    )
    (net (code "109") (name "unconnected-(U1-PD2(INT0)-Pad4)") (class "Default")
      (node (ref "U1") (pin "4") (pinfunction "PD2(INT0)_4") (pintype "bidirectional"))
    )
    (net (code "110") (name "unconnected-(U1-PD4(XCK{slash}T0)-Pad6)") (class "Default")
      (node (ref "U1") (pin "6") (pinfunction "PD4(XCK/T0)_6") (pintype "bidirectional"))
    )
    (net (code "111") (name "unconnected-(U1-PD5(T1)-Pad11)") (class "Default")
      (node (ref "U1") (pin "11") (pinfunction "PD5(T1)_11") (pintype "bidirectional"))
    )
    (net (code "112") (name "unconnected-(U1-PD6(AIN0)-Pad12)") (class "Default")
      (node (ref "U1") (pin "12") (pinfunction "PD6(AIN0)_12") (pintype "bidirectional"))
    )
    (net (code "113") (name "unconnected-(U1-PD7(AIN1)-Pad13)") (class "Default")
      (node (ref "U1") (pin "13") (pinfunction "PD7(AIN1)_13") (pintype "bidirectional"))
    )
    (net (code "114") (name "unconnected-(X1A-KL-Pad1)") (class "Default")
      (node (ref "X1") (pin "1") (pinfunction "KL_1") (pintype "passive"))
    )
    (net (code "115") (name "unconnected-(X2A-KL-Pad1)") (class "Default")
      (node (ref "X2") (pin "1") (pinfunction "KL_1") (pintype "passive"))
    )
    (net (code "116") (name "unconnected-(X3A-KL-Pad1)") (class "Default")
      (node (ref "X3") (pin "1") (pinfunction "KL_1") (pintype "passive"))
    )
    (net (code "117") (name "unconnected-(X4A-KL-Pad1)") (class "Default")
      (node (ref "X4") (pin "1") (pinfunction "KL_1") (pintype "passive"))
    )
    (net (code "118") (name "unconnected-(X5A-KL-Pad1)") (class "Default")
      (node (ref "X5") (pin "1") (pinfunction "KL_1") (pintype "passive"))
    )
    (net (code "119") (name "unconnected-(X6A-KL-Pad1)") (class "Default")
      (node (ref "X6") (pin "1") (pinfunction "KL_1") (pintype "passive"))
    )
    (net (code "120") (name "unconnected-(X7A-KL-Pad1)") (class "Default")
      (node (ref "X7") (pin "1") (pinfunction "KL_1") (pintype "passive"))
    )
    (net (code "121") (name "unconnected-(X8A-KL-Pad1)") (class "Default")
      (node (ref "X8") (pin "1") (pinfunction "KL_1") (pintype "passive"))
    )
  )
)
